# Bridge.net
KiCad netlist of a schematic drawn in Altium Designer
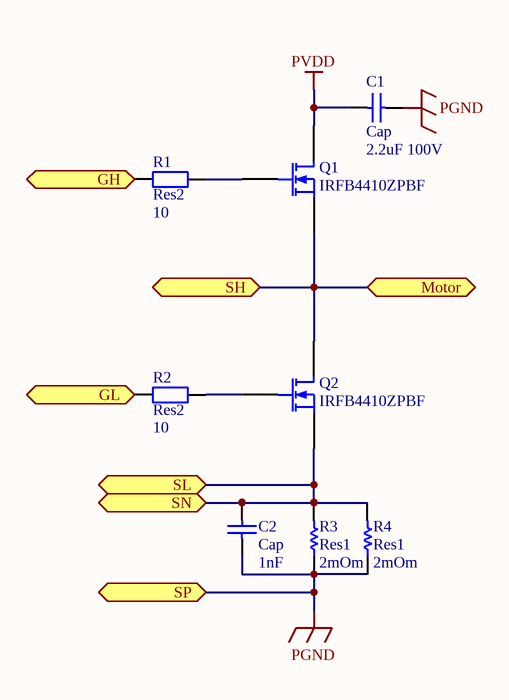
[diagram p0: Bridge.SchDoc]

(export (version "E")
  (design (tool "Eeschema 10.0.6"))
  (components
    (comp (ref "C1")
      (value "Cap")
      (footprint "RAD-0.3")
      (description "Capacitor")
      (fields (field (name "ALTIUM_VALUE") "2.2uF 100V") (field (name "PUBLISHER") "Altium Limited"))
      (libsource (lib "Miscellaneous Devices") (part "Cap"))
    )
    (comp (ref "C2")
      (value "Cap")
      (footprint "RAD-0.3")
      (description "Capacitor")
      (fields (field (name "ALTIUM_VALUE") "1nF") (field (name "PUBLISHER") "Altium Limited"))
      (libsource (lib "Miscellaneous Devices") (part "Cap"))
    )
    (comp (ref "Q1")
      (value "IRFB4410ZPBF")
      (footprint "TO-220AB")
      (fields (field (name "PUBLISHER") "Altium Limited"))
      (libsource (lib "Miscellaneous Devices") (part "MOSFET-N"))
    )
    (comp (ref "Q2")
      (value "IRFB4410ZPBF")
      (footprint "TO-220AB")
      (fields (field (name "PUBLISHER") "Altium Limited"))
      (libsource (lib "Miscellaneous Devices") (part "MOSFET-N"))
    )
    (comp (ref "R1")
      (value "Res2")
      (footprint "6-0805_N")
      (description "Resistor")
      (fields (field (name "ALTIUM_VALUE") "10") (field (name "PUBLISHER") "Altium Limited"))
      (libsource (lib "Miscellaneous Devices") (part "Res2"))
    )
    (comp (ref "R2")
      (value "Res2")
      (footprint "6-0805_N")
      (description "Resistor")
      (fields (field (name "ALTIUM_VALUE") "10") (field (name "PUBLISHER") "Altium Limited"))
      (libsource (lib "Miscellaneous Devices") (part "Res2"))
    )
    (comp (ref "R3")
      (value "Res1")
      (footprint "AXIAL-0.3")
      (description "Resistor")
      (fields (field (name "ALTIUM_VALUE") "2mOm") (field (name "PUBLISHER") "Altium Limited"))
      (libsource (lib "Miscellaneous Devices") (part "Res1"))
    )
    (comp (ref "R4")
      (value "Res1")
      (footprint "AXIAL-0.3")
      (description "Resistor")
      (fields (field (name "ALTIUM_VALUE") "2mOm") (field (name "PUBLISHER") "Altium Limited"))
      (libsource (lib "Miscellaneous Devices") (part "Res1"))
    )
  )
  (nets
    (net (code "1") (name "/GH") (class "Default")
      (node (ref "R1") (pin "1") (pinfunction "1_1") (pintype "passive"))
    )
    (net (code "2") (name "/GL") (class "Default")
      (node (ref "R2") (pin "1") (pinfunction "1_1") (pintype "passive"))
    )
    (net (code "3") (name "/Motor") (class "Default")
      (node (ref "Q1") (pin "3") (pinfunction "S_3") (pintype "passive"))
      (node (ref "Q2") (pin "1") (pinfunction "D_1") (pintype "passive"))
    )
    (net (code "4") (name "/SL") (class "Default")
      (node (ref "C2") (pin "2") (pinfunction "2_2") (pintype "passive"))
      (node (ref "Q2") (pin "3") (pinfunction "S_3") (pintype "passive"))
      (node (ref "R3") (pin "2") (pinfunction "2_2") (pintype "passive"))
      (node (ref "R4") (pin "2") (pinfunction "2_2") (pintype "passive"))
    )
    (net (code "5") (name "Net-(Q1-G)") (class "Default")
      (node (ref "Q1") (pin "2") (pinfunction "G_2") (pintype "passive"))
      (node (ref "R1") (pin "2") (pinfunction "2_2") (pintype "passive"))
    )
    (net (code "6") (name "Net-(Q2-G)") (class "Default")
      (node (ref "Q2") (pin "2") (pinfunction "G_2") (pintype "passive"))
      (node (ref "R2") (pin "2") (pinfunction "2_2") (pintype "passive"))
    )
    (net (code "7") (name "PGND") (class "Default")
      (node (ref "C1") (pin "1") (pinfunction "1_1") (pintype "passive"))
      (node (ref "C2") (pin "1") (pinfunction "1_1") (pintype "passive"))
      (node (ref "R3") (pin "1") (pinfunction "1_1") (pintype "passive"))
      (node (ref "R4") (pin "1") (pinfunction "1_1") (pintype "passive"))
    )
    (net (code "8") (name "PVDD") (class "Default")
      (node (ref "C1") (pin "2") (pinfunction "2_2") (pintype "passive"))
      (node (ref "Q1") (pin "1") (pinfunction "D_1") (pintype "passive"))
    )
  )
)
